# sunburn-monitor-v2.net
KiCad netlist of a schematic drawn in EAGLE
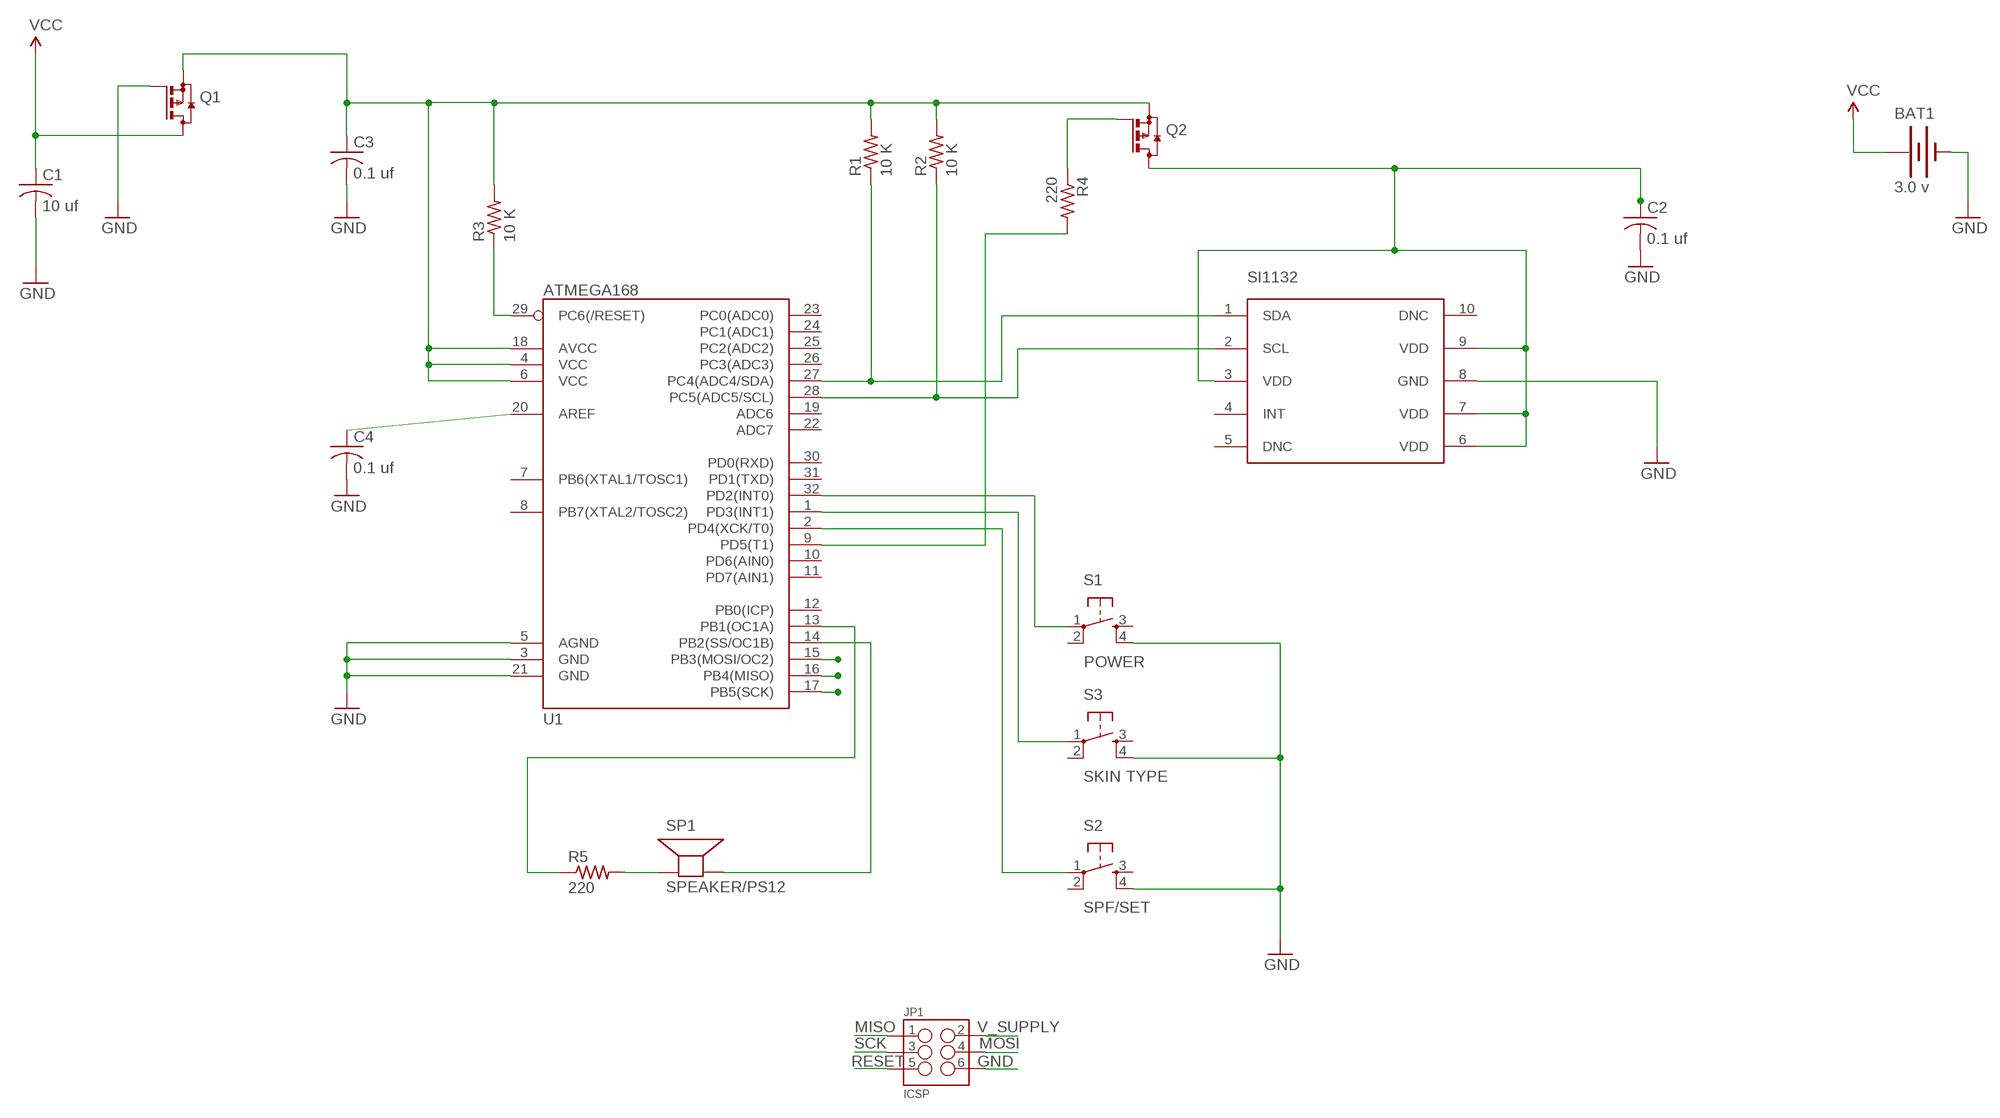
[diagram p0: schematic, sheet 1]

(export (version "E")
  (design (tool "Eeschema 10.0.6"))
  (components
    (comp (ref "BAT1")
      (value "3.0 v")
      (footprint "eagle-import:BATTCON_20MM")
      (libsource (lib "eagle-import") (part "BATTERY20SMD"))
    )
    (comp (ref "C1")
      (value "10 uf")
      (footprint "eagle-import:C2012")
      (libsource (lib "eagle-import") (part "C-USC2012"))
    )
    (comp (ref "C2")
      (value "0.1 uf")
      (footprint "eagle-import:C2012")
      (libsource (lib "eagle-import") (part "C-USC2012"))
    )
    (comp (ref "C3")
      (value "0.1 uf")
      (footprint "eagle-import:C2012")
      (libsource (lib "eagle-import") (part "C-USC2012"))
    )
    (comp (ref "C4")
      (value "0.1 uf")
      (footprint "eagle-import:C2012")
      (libsource (lib "eagle-import") (part "C-USC2012"))
    )
    (comp (ref "JP1")
      (value "ICSP")
      (footprint "eagle-import:2X3-NS")
      (libsource (lib "eagle-import") (part "M03X2NO_SILK"))
    )
    (comp (ref "Q1")
      (value "SI2333DDS")
      (footprint "eagle-import:SOT23")
      (libsource (lib "eagle-import") (part "SI2333DDS"))
    )
    (comp (ref "Q2")
      (value "SI2333DDS")
      (footprint "eagle-import:SOT23")
      (libsource (lib "eagle-import") (part "SI2333DDS"))
    )
    (comp (ref "R1")
      (value "10 K")
      (footprint "eagle-import:R2012")
      (libsource (lib "eagle-import") (part "R-US_R2012"))
    )
    (comp (ref "R2")
      (value "10 K")
      (footprint "eagle-import:R2012")
      (libsource (lib "eagle-import") (part "R-US_R2012"))
    )
    (comp (ref "R3")
      (value "10 K")
      (footprint "eagle-import:R2012")
      (libsource (lib "eagle-import") (part "R-US_R2012"))
    )
    (comp (ref "R4")
      (value "220")
      (footprint "eagle-import:R2012")
      (libsource (lib "eagle-import") (part "R-US_R2012"))
    )
    (comp (ref "R5")
      (value "220")
      (footprint "eagle-import:R2012")
      (libsource (lib "eagle-import") (part "R-US_R2012"))
    )
    (comp (ref "S1")
      (value "POWER")
      (footprint "eagle-import:TACTILE_SWITCH_SMD")
      (libsource (lib "eagle-import") (part "TAC_SWITCHSMD"))
    )
    (comp (ref "S2")
      (value "SPF/SET")
      (footprint "eagle-import:TACTILE_SWITCH_SMD")
      (libsource (lib "eagle-import") (part "TAC_SWITCHSMD"))
    )
    (comp (ref "S3")
      (value "SKIN TYPE")
      (footprint "eagle-import:TACTILE_SWITCH_SMD")
      (libsource (lib "eagle-import") (part "TAC_SWITCHSMD"))
    )
    (comp (ref "SP1")
      (value "SPEAKER/PS12")
      (footprint "eagle-import:PS12")
      (libsource (lib "eagle-import") (part "SPEAKER/PS12"))
    )
    (comp (ref "U1")
      (value "ATMEGA168")
      (footprint "eagle-import:TQFP32-08")
      (libsource (lib "eagle-import") (part "ATMEGA168"))
    )
    (comp (ref "U2")
      (value "SI1132")
      (footprint "eagle-import:QFN-10")
      (libsource (lib "eagle-import") (part "SI1132"))
    )
  )
  (nets
    (net (code "1") (name "/MISO") (class "Default")
      (node (ref "JP1") (pin "1") (pinfunction "1_1") (pintype "bidirectional"))
      (node (ref "U1") (pin "16") (pinfunction "PB4(MISO)_16") (pintype "bidirectional"))
    )
    (net (code "2") (name "/MOSI") (class "Default")
      (node (ref "JP1") (pin "4") (pinfunction "4_4") (pintype "bidirectional"))
      (node (ref "U1") (pin "15") (pinfunction "PB3(MOSI/OC2)_15") (pintype "bidirectional"))
    )
    (net (code "3") (name "/RESET") (class "Default")
      (node (ref "JP1") (pin "5") (pinfunction "5_5") (pintype "bidirectional"))
      (node (ref "R3") (pin "1") (pinfunction "1_1") (pintype "passive"))
      (node (ref "U1") (pin "29") (pinfunction "PC6(/RESET)_29") (pintype "bidirectional"))
    )
    (net (code "4") (name "/SCK") (class "Default")
      (node (ref "JP1") (pin "3") (pinfunction "3_3") (pintype "bidirectional"))
      (node (ref "U1") (pin "17") (pinfunction "PB5(SCK)_17") (pintype "bidirectional"))
    )
    (net (code "5") (name "/V_SUPPLY") (class "Default")
      (node (ref "C3") (pin "1") (pinfunction "1_1") (pintype "passive"))
      (node (ref "JP1") (pin "2") (pinfunction "2_2") (pintype "bidirectional"))
      (node (ref "Q1") (pin "2") (pinfunction "S_2") (pintype "passive"))
      (node (ref "Q2") (pin "2") (pinfunction "S_2") (pintype "passive"))
      (node (ref "R1") (pin "2") (pinfunction "2_2") (pintype "passive"))
      (node (ref "R2") (pin "2") (pinfunction "2_2") (pintype "passive"))
      (node (ref "R3") (pin "2") (pinfunction "2_2") (pintype "passive"))
      (node (ref "U1") (pin "18") (pinfunction "AVCC_18") (pintype "bidirectional"))
      (node (ref "U1") (pin "4") (pinfunction "VCC_4") (pintype "bidirectional"))
      (node (ref "U1") (pin "6") (pinfunction "VCC_6") (pintype "bidirectional"))
    )
    (net (code "6") (name "GND") (class "Default")
      (node (ref "BAT1") (pin "2") (pinfunction "-_2") (pintype "power_in"))
      (node (ref "C1") (pin "2") (pinfunction "2_2") (pintype "passive"))
      (node (ref "C2") (pin "2") (pinfunction "2_2") (pintype "passive"))
      (node (ref "C3") (pin "2") (pinfunction "2_2") (pintype "passive"))
      (node (ref "C4") (pin "2") (pinfunction "2_2") (pintype "passive"))
      (node (ref "JP1") (pin "6") (pinfunction "6_6") (pintype "bidirectional"))
      (node (ref "Q1") (pin "1") (pinfunction "G_1") (pintype "passive"))
      (node (ref "S1") (pin "4") (pinfunction "4_4") (pintype "passive"))
      (node (ref "S2") (pin "4") (pinfunction "4_4") (pintype "passive"))
      (node (ref "S3") (pin "4") (pinfunction "4_4") (pintype "passive"))
      (node (ref "U1") (pin "21") (pinfunction "GND_21") (pintype "bidirectional"))
      (node (ref "U1") (pin "3") (pinfunction "GND_3") (pintype "bidirectional"))
      (node (ref "U1") (pin "5") (pinfunction "AGND_5") (pintype "bidirectional"))
      (node (ref "U2") (pin "8") (pinfunction "GND_8") (pintype "power_in"))
    )
    (net (code "7") (name "Net-(Q2-D)") (class "Default")
      (node (ref "C2") (pin "1") (pinfunction "1_1") (pintype "passive"))
      (node (ref "Q2") (pin "3") (pinfunction "D_3") (pintype "passive"))
      (node (ref "U2") (pin "3") (pinfunction "VDD_3") (pintype "power_in"))
      (node (ref "U2") (pin "6") (pinfunction "VDD_6") (pintype "power_in"))
      (node (ref "U2") (pin "7") (pinfunction "VDD_7") (pintype "power_in"))
      (node (ref "U2") (pin "9") (pinfunction "VDD_9") (pintype "power_in"))
    )
    (net (code "8") (name "Net-(Q2-G)") (class "Default")
      (node (ref "Q2") (pin "1") (pinfunction "G_1") (pintype "passive"))
      (node (ref "R4") (pin "1") (pinfunction "1_1") (pintype "passive"))
    )
    (net (code "9") (name "Net-(SP1-+)") (class "Default")
      (node (ref "R5") (pin "2") (pinfunction "2_2") (pintype "passive"))
      (node (ref "SP1") (pin "P$1") (pinfunction "+_P$1") (pintype "passive"))
    )
    (net (code "10") (name "Net-(SP1--)") (class "Default")
      (node (ref "SP1") (pin "P$2") (pinfunction "-_P$2") (pintype "passive"))
      (node (ref "U1") (pin "14") (pinfunction "PB2(SS/OC1B)_14") (pintype "bidirectional"))
    )
    (net (code "11") (name "Net-(U1-AREF)") (class "Default")
      (node (ref "C4") (pin "1") (pinfunction "1_1") (pintype "passive"))
      (node (ref "U1") (pin "20") (pinfunction "AREF_20") (pintype "bidirectional"))
    )
    (net (code "12") (name "Net-(U1-PB1(OC1A))") (class "Default")
      (node (ref "R5") (pin "1") (pinfunction "1_1") (pintype "passive"))
      (node (ref "U1") (pin "13") (pinfunction "PB1(OC1A)_13") (pintype "bidirectional"))
    )
    (net (code "13") (name "Net-(U1-PC4(ADC4{slash}SDA))") (class "Default")
      (node (ref "R1") (pin "1") (pinfunction "1_1") (pintype "passive"))
      (node (ref "U1") (pin "27") (pinfunction "PC4(ADC4/SDA)_27") (pintype "bidirectional"))
      (node (ref "U2") (pin "1") (pinfunction "SDA_1") (pintype "bidirectional"))
    )
    (net (code "14") (name "Net-(U1-PC5(ADC5{slash}SCL))") (class "Default")
      (node (ref "R2") (pin "1") (pinfunction "1_1") (pintype "passive"))
      (node (ref "U1") (pin "28") (pinfunction "PC5(ADC5/SCL)_28") (pintype "bidirectional"))
      (node (ref "U2") (pin "2") (pinfunction "SCL_2") (pintype "bidirectional"))
    )
    (net (code "15") (name "Net-(U1-PD2(INT0))") (class "Default")
      (node (ref "S1") (pin "1") (pinfunction "1_1") (pintype "passive"))
      (node (ref "U1") (pin "32") (pinfunction "PD2(INT0)_32") (pintype "bidirectional"))
    )
    (net (code "16") (name "Net-(U1-PD3(INT1))") (class "Default")
      (node (ref "S3") (pin "1") (pinfunction "1_1") (pintype "passive"))
      (node (ref "U1") (pin "1") (pinfunction "PD3(INT1)_1") (pintype "bidirectional"))
    )
    (net (code "17") (name "Net-(U1-PD4(XCK{slash}T0))") (class "Default")
      (node (ref "S2") (pin "1") (pinfunction "1_1") (pintype "passive"))
      (node (ref "U1") (pin "2") (pinfunction "PD4(XCK/T0)_2") (pintype "bidirectional"))
    )
    (net (code "18") (name "Net-(U1-PD5(T1))") (class "Default")
      (node (ref "R4") (pin "2") (pinfunction "2_2") (pintype "passive"))
      (node (ref "U1") (pin "9") (pinfunction "PD5(T1)_9") (pintype "bidirectional"))
    )
    (net (code "19") (name "VCC") (class "Default")
      (node (ref "BAT1") (pin "1") (pinfunction "+_1") (pintype "power_in"))
      (node (ref "C1") (pin "1") (pinfunction "1_1") (pintype "passive"))
      (node (ref "Q1") (pin "3") (pinfunction "D_3") (pintype "passive"))
    )
    (net (code "20") (name "unconnected-(S1-Pad2)") (class "Default")
      (node (ref "S1") (pin "2") (pinfunction "2_2") (pintype "passive"))
    )
    (net (code "21") (name "unconnected-(S1-Pad3)") (class "Default")
      (node (ref "S1") (pin "3") (pinfunction "3_3") (pintype "passive"))
    )
    (net (code "22") (name "unconnected-(S2-Pad2)") (class "Default")
      (node (ref "S2") (pin "2") (pinfunction "2_2") (pintype "passive"))
    )
    (net (code "23") (name "unconnected-(S2-Pad3)") (class "Default")
      (node (ref "S2") (pin "3") (pinfunction "3_3") (pintype "passive"))
    )
    (net (code "24") (name "unconnected-(S3-Pad2)") (class "Default")
      (node (ref "S3") (pin "2") (pinfunction "2_2") (pintype "passive"))
    )
    (net (code "25") (name "unconnected-(S3-Pad3)") (class "Default")
      (node (ref "S3") (pin "3") (pinfunction "3_3") (pintype "passive"))
    )
    (net (code "26") (name "unconnected-(U1-ADC6-Pad19)") (class "Default")
      (node (ref "U1") (pin "19") (pinfunction "ADC6_19") (pintype "bidirectional"))
    )
    (net (code "27") (name "unconnected-(U1-ADC7-Pad22)") (class "Default")
      (node (ref "U1") (pin "22") (pinfunction "ADC7_22") (pintype "bidirectional"))
    )
    (net (code "28") (name "unconnected-(U1-PB0(ICP)-Pad12)") (class "Default")
      (node (ref "U1") (pin "12") (pinfunction "PB0(ICP)_12") (pintype "bidirectional"))
    )
    (net (code "29") (name "unconnected-(U1-PB6(XTAL1{slash}TOSC1)-Pad7)") (class "Default")
      (node (ref "U1") (pin "7") (pinfunction "PB6(XTAL1/TOSC1)_7") (pintype "bidirectional"))
    )
    (net (code "30") (name "unconnected-(U1-PB7(XTAL2{slash}TOSC2)-Pad8)") (class "Default")
      (node (ref "U1") (pin "8") (pinfunction "PB7(XTAL2/TOSC2)_8") (pintype "bidirectional"))
    )
    (net (code "31") (name "unconnected-(U1-PC0(ADC0)-Pad23)") (class "Default")
      (node (ref "U1") (pin "23") (pinfunction "PC0(ADC0)_23") (pintype "bidirectional"))
    )
    (net (code "32") (name "unconnected-(U1-PC1(ADC1)-Pad24)") (class "Default")
      (node (ref "U1") (pin "24") (pinfunction "PC1(ADC1)_24") (pintype "bidirectional"))
    )
    (net (code "33") (name "unconnected-(U1-PC2(ADC2)-Pad25)") (class "Default")
      (node (ref "U1") (pin "25") (pinfunction "PC2(ADC2)_25") (pintype "bidirectional"))
    )
    (net (code "34") (name "unconnected-(U1-PC3(ADC3)-Pad26)") (class "Default")
      (node (ref "U1") (pin "26") (pinfunction "PC3(ADC3)_26") (pintype "bidirectional"))
    )
    (net (code "35") (name "unconnected-(U1-PD0(RXD)-Pad30)") (class "Default")
      (node (ref "U1") (pin "30") (pinfunction "PD0(RXD)_30") (pintype "bidirectional"))
    )
    (net (code "36") (name "unconnected-(U1-PD1(TXD)-Pad31)") (class "Default")
      (node (ref "U1") (pin "31") (pinfunction "PD1(TXD)_31") (pintype "bidirectional"))
    )
    (net (code "37") (name "unconnected-(U1-PD6(AIN0)-Pad10)") (class "Default")
      (node (ref "U1") (pin "10") (pinfunction "PD6(AIN0)_10") (pintype "bidirectional"))
    )
    (net (code "38") (name "unconnected-(U1-PD7(AIN1)-Pad11)") (class "Default")
      (node (ref "U1") (pin "11") (pinfunction "PD7(AIN1)_11") (pintype "bidirectional"))
    )
    (net (code "39") (name "unconnected-(U2-DNC-Pad5)") (class "Default")
      (node (ref "U2") (pin "5") (pinfunction "DNC_5") (pintype "no_connect"))
    )
    (net (code "40") (name "unconnected-(U2-DNC-Pad10)") (class "Default")
      (node (ref "U2") (pin "10") (pinfunction "DNC_10") (pintype "no_connect"))
    )
    (net (code "41") (name "unconnected-(U2-INT-Pad4)") (class "Default")
      (node (ref "U2") (pin "4") (pinfunction "INT_4") (pintype "bidirectional"))
    )
  )
)
